# Power_Supply_Gating.net
KiCad netlist of a schematic drawn in EAGLE
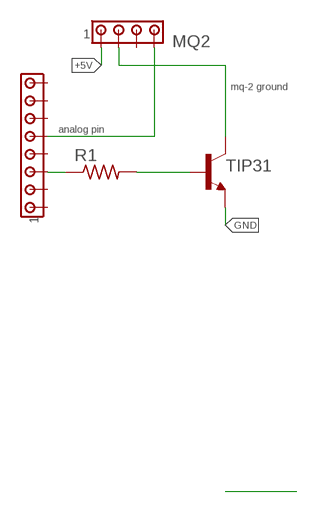
[diagram p0: schematic, sheet 1]

(export (version "E")
  (design (tool "Eeschema 10.0.6"))
  (components
    (comp (ref "MIC_KANAN")
      (value "MTA08-100")
      (footprint "eagle-import:10X08MTA")
      (libsource (lib "eagle-import") (part "MTA08-100"))
    )
    (comp (ref "MQ2")
      (value "MTA04-100")
      (footprint "eagle-import:10X04MTA")
      (libsource (lib "eagle-import") (part "MTA04-100"))
    )
    (comp (ref "R1")
      (value "560")
      (footprint "eagle-import:0204_7")
      (libsource (lib "eagle-import") (part "R-US_0204/7"))
    )
    (comp (ref "TIP31")
      (value "2SC1306")
      (footprint "eagle-import:TO220BV")
      (libsource (lib "eagle-import") (part "2SC1306"))
    )
  )
  (nets
    (net (code "1") (name "+5V") (class "Default")
      (node (ref "MQ2") (pin "1") (pinfunction "1_1") (pintype "passive"))
    )
    (net (code "2") (name "GND") (class "Default")
      (node (ref "TIP31") (pin "3") (pinfunction "E_3") (pintype "passive"))
    )
    (net (code "3") (name "Net-(MIC_KANAN-Pad3)") (class "Default")
      (node (ref "MIC_KANAN") (pin "3") (pinfunction "3_3") (pintype "passive"))
      (node (ref "R1") (pin "1") (pinfunction "1_1") (pintype "passive"))
    )
    (net (code "4") (name "Net-(MIC_KANAN-Pad5)") (class "Default")
      (node (ref "MIC_KANAN") (pin "5") (pinfunction "5_5") (pintype "passive"))
      (node (ref "MQ2") (pin "4") (pinfunction "4_4") (pintype "passive"))
    )
    (net (code "5") (name "Net-(TIP31-B)") (class "Default")
      (node (ref "R1") (pin "2") (pinfunction "2_2") (pintype "passive"))
      (node (ref "TIP31") (pin "1") (pinfunction "B_1") (pintype "passive"))
    )
    (net (code "6") (name "Net-(TIP31-C)") (class "Default")
      (node (ref "MQ2") (pin "2") (pinfunction "2_2") (pintype "passive"))
      (node (ref "TIP31") (pin "2") (pinfunction "C_2") (pintype "passive"))
    )
    (net (code "7") (name "unconnected-(MIC_KANAN-Pad1)") (class "Default")
      (node (ref "MIC_KANAN") (pin "1") (pinfunction "1_1") (pintype "passive"))
    )
    (net (code "8") (name "unconnected-(MIC_KANAN-Pad2)") (class "Default")
      (node (ref "MIC_KANAN") (pin "2") (pinfunction "2_2") (pintype "passive"))
    )
    (net (code "9") (name "unconnected-(MIC_KANAN-Pad4)") (class "Default")
      (node (ref "MIC_KANAN") (pin "4") (pinfunction "4_4") (pintype "passive"))
    )
    (net (code "10") (name "unconnected-(MIC_KANAN-Pad6)") (class "Default")
      (node (ref "MIC_KANAN") (pin "6") (pinfunction "6_6") (pintype "passive"))
    )
    (net (code "11") (name "unconnected-(MIC_KANAN-Pad7)") (class "Default")
      (node (ref "MIC_KANAN") (pin "7") (pinfunction "7_7") (pintype "passive"))
    )
    (net (code "12") (name "unconnected-(MIC_KANAN-Pad8)") (class "Default")
      (node (ref "MIC_KANAN") (pin "8") (pinfunction "8_8") (pintype "passive"))
    )
    (net (code "13") (name "unconnected-(MQ2-Pad3)") (class "Default")
      (node (ref "MQ2") (pin "3") (pinfunction "3_3") (pintype "passive"))
    )
  )
)
